# ARC_Shield_0_1.net
KiCad netlist of a schematic drawn in EAGLE
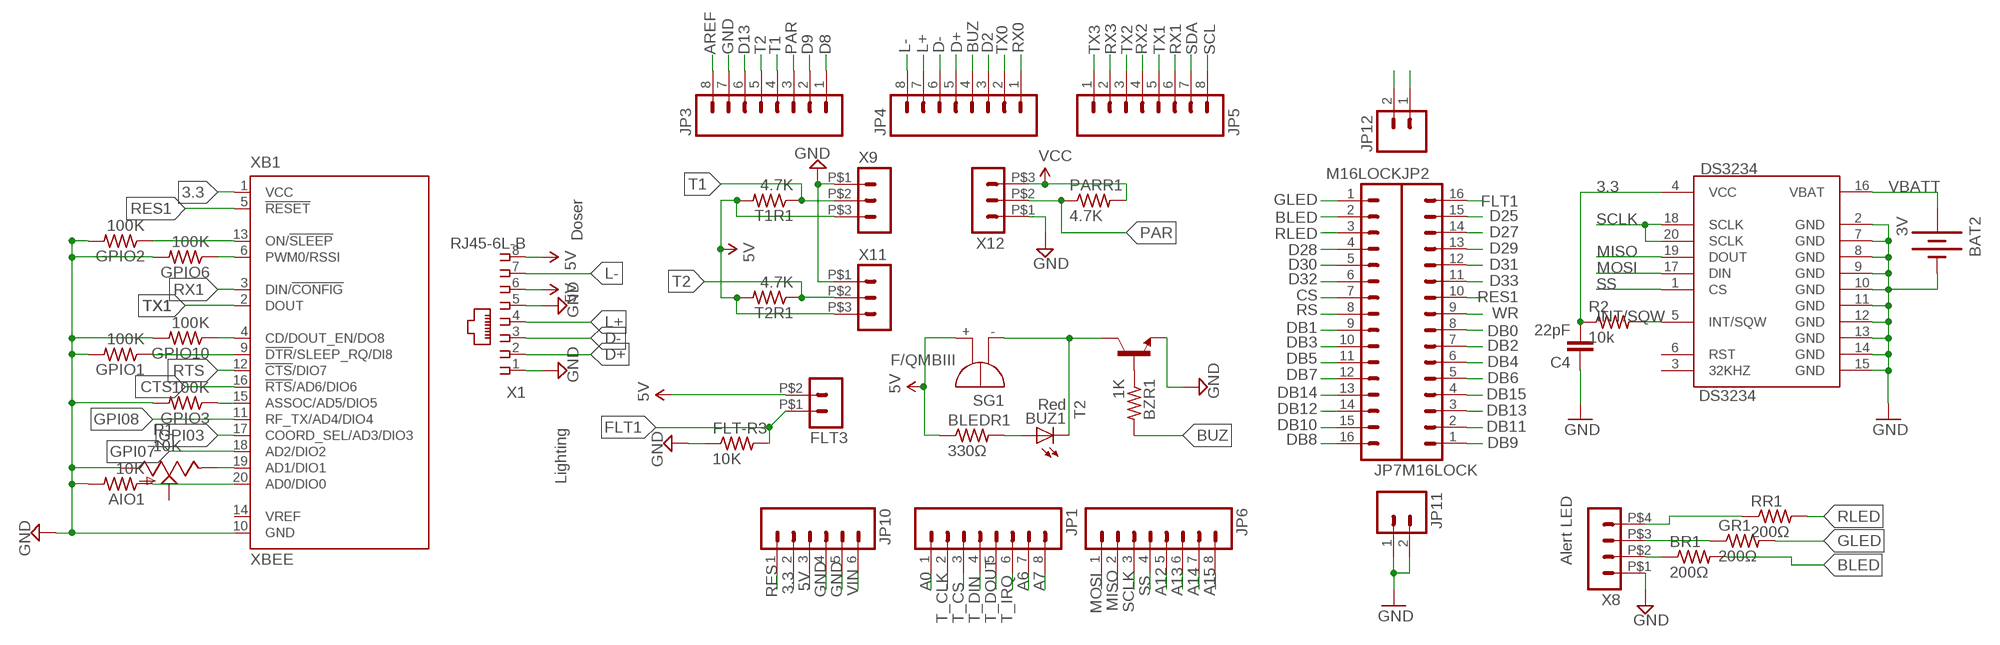
[diagram p0: schematic, sheet 1]

(export (version "E")
  (design (tool "Eeschema 10.0.6"))
  (components
    (comp (ref "AIO1")
      (value "10K")
      (footprint "eagle-import:0204_7")
      (libsource (lib "eagle-import") (part "R-US_0204/7"))
    )
    (comp (ref "BAT2")
      (value "3V")
      (footprint "eagle-import:BATTCON_12MM_CURVED")
      (libsource (lib "eagle-import") (part "BATTERY"))
    )
    (comp (ref "BLEDR1")
      (value "330Ω")
      (footprint "eagle-import:0204_7")
      (libsource (lib "eagle-import") (part "R-US_0204/7"))
    )
    (comp (ref "BR1")
      (value "200Ω")
      (footprint "eagle-import:0204_7")
      (libsource (lib "eagle-import") (part "R-US_0204/7"))
    )
    (comp (ref "BUZ1")
      (value "Red")
      (footprint "eagle-import:LED3MM")
      (libsource (lib "eagle-import") (part "LED3MM"))
    )
    (comp (ref "BZR1")
      (value "1K")
      (footprint "eagle-import:0204_7")
      (libsource (lib "eagle-import") (part "R-US_0204/7"))
    )
    (comp (ref "C4")
      (value "22pF")
      (footprint "eagle-import:C5B3")
      (libsource (lib "eagle-import") (part "C5/3"))
    )
    (comp (ref "DS3234")
      (value "DS3234")
      (footprint "eagle-import:DS3234")
      (libsource (lib "eagle-import") (part "DS3234"))
    )
    (comp (ref "FLT-R3")
      (value "10K")
      (footprint "eagle-import:0204_7")
      (libsource (lib "eagle-import") (part "R-US_0204/7"))
    )
    (comp (ref "FLT3")
      (value "HEADER_POS2_43045-0200")
      (footprint "eagle-import:43045-0200")
      (libsource (lib "eagle-import") (part "HEADER_POS2_?43045-0200"))
    )
    (comp (ref "GPIO1")
      (value "100K")
      (footprint "eagle-import:0204_7")
      (libsource (lib "eagle-import") (part "R-US_0204/7"))
    )
    (comp (ref "GPIO2")
      (value "100K")
      (footprint "eagle-import:0204_7")
      (libsource (lib "eagle-import") (part "R-US_0204/7"))
    )
    (comp (ref "GPIO3")
      (value "100K")
      (footprint "eagle-import:0204_7")
      (libsource (lib "eagle-import") (part "R-US_0204/7"))
    )
    (comp (ref "GPIO6")
      (value "100K")
      (footprint "eagle-import:0204_7")
      (libsource (lib "eagle-import") (part "R-US_0204/7"))
    )
    (comp (ref "GPIO10")
      (value "100K")
      (footprint "eagle-import:0204_7")
      (libsource (lib "eagle-import") (part "R-US_0204/7"))
    )
    (comp (ref "GR1")
      (value "200Ω")
      (footprint "eagle-import:0204_7")
      (libsource (lib "eagle-import") (part "R-US_0204/7"))
    )
    (comp (ref "JP1")
      (value "M08LOCK")
      (footprint "eagle-import:1X08_LOCK")
      (libsource (lib "eagle-import") (part "M08LOCK"))
    )
    (comp (ref "JP2")
      (value "M16LOCK")
      (footprint "eagle-import:1X16_LOCK")
      (libsource (lib "eagle-import") (part "M16LOCK"))
    )
    (comp (ref "JP3")
      (value "M08LOCK")
      (footprint "eagle-import:1X08_LOCK")
      (libsource (lib "eagle-import") (part "M08LOCK"))
    )
    (comp (ref "JP4")
      (value "M08LOCK")
      (footprint "eagle-import:1X08_LOCK")
      (libsource (lib "eagle-import") (part "M08LOCK"))
    )
    (comp (ref "JP5")
      (value "M08LOCK")
      (footprint "eagle-import:1X08_LOCK")
      (libsource (lib "eagle-import") (part "M08LOCK"))
    )
    (comp (ref "JP6")
      (value "M08LOCK")
      (footprint "eagle-import:1X08_LOCK")
      (libsource (lib "eagle-import") (part "M08LOCK"))
    )
    (comp (ref "JP7")
      (value "M16LOCK")
      (footprint "eagle-import:1X16_LOCK")
      (libsource (lib "eagle-import") (part "M16LOCK"))
    )
    (comp (ref "JP10")
      (value "M06LOCK")
      (footprint "eagle-import:1X06_LOCK")
      (libsource (lib "eagle-import") (part "M06LOCK"))
    )
    (comp (ref "JP11")
      (value "M02LOCK")
      (footprint "eagle-import:1X02_LOCK")
      (libsource (lib "eagle-import") (part "M02LOCK"))
    )
    (comp (ref "JP12")
      (value "M02LOCK")
      (footprint "eagle-import:1X02_LOCK")
      (libsource (lib "eagle-import") (part "M02LOCK"))
    )
    (comp (ref "PARR1")
      (value "4.7K")
      (footprint "eagle-import:0204_7")
      (libsource (lib "eagle-import") (part "R-US_0204/7"))
    )
    (comp (ref "R1")
      (value "10K")
      (footprint "eagle-import:B25U")
      (libsource (lib "eagle-import") (part "TRIM_US-B25U"))
    )
    (comp (ref "R2")
      (value "10k")
      (footprint "eagle-import:0204_7")
      (libsource (lib "eagle-import") (part "R-US_0204/7"))
    )
    (comp (ref "RR1")
      (value "200Ω")
      (footprint "eagle-import:0204_7")
      (libsource (lib "eagle-import") (part "R-US_0204/7"))
    )
    (comp (ref "SG1")
      (value "F/QMBIII")
      (footprint "eagle-import:F_QMBIII")
      (libsource (lib "eagle-import") (part "F/QMBIII"))
    )
    (comp (ref "T1R1")
      (value "4.7K")
      (footprint "eagle-import:0204_7")
      (libsource (lib "eagle-import") (part "R-US_0204/7"))
    )
    (comp (ref "T2")
      (value "-NPN-TO92")
      (footprint "eagle-import:TO92")
      (libsource (lib "eagle-import") (part "-NPN-TO92"))
    )
    (comp (ref "T2R1")
      (value "4.7K")
      (footprint "eagle-import:0204_7")
      (libsource (lib "eagle-import") (part "R-US_0204/7"))
    )
    (comp (ref "X1")
      (value "RJ45-6L-B")
      (footprint "eagle-import:RJ45-NO-SHIELD")
      (libsource (lib "eagle-import") (part "RJ45-6L-B"))
    )
    (comp (ref "X8")
      (value "HEADER_POS4_43045-0401")
      (footprint "eagle-import:43045-0400")
      (libsource (lib "eagle-import") (part "HEADER_POS4_?43045-0401"))
    )
    (comp (ref "X9")
      (value "HEADER_POS3_43650-0300")
      (footprint "eagle-import:43650-0300")
      (libsource (lib "eagle-import") (part "HEADER_POS3_?43650-0300"))
    )
    (comp (ref "X11")
      (value "HEADER_POS3_43650-0300")
      (footprint "eagle-import:43650-0300")
      (libsource (lib "eagle-import") (part "HEADER_POS3_?43650-0300"))
    )
    (comp (ref "X12")
      (value "HEADER_POS3_43650-0300")
      (footprint "eagle-import:43650-0300")
      (libsource (lib "eagle-import") (part "HEADER_POS3_?43650-0300"))
    )
    (comp (ref "XB1")
      (value "XBEE")
      (footprint "eagle-import:XBEE")
      (fields (field (name "MPN") "XBP24-Z7UIT-004"))
      (libsource (lib "eagle-import") (part "XBEE"))
    )
  )
  (nets
    (net (code "1") (name "/5V@1") (class "Default")
      (node (ref "JP12") (pin "1") (pinfunction "1_1") (pintype "passive"))
      (node (ref "JP12") (pin "2") (pinfunction "2_2") (pintype "passive"))
    )
    (net (code "2") (name "/A0") (class "Default")
      (node (ref "JP1") (pin "1") (pinfunction "1_1") (pintype "passive"))
    )
    (net (code "3") (name "/A6") (class "Default")
      (node (ref "JP1") (pin "7") (pinfunction "7_7") (pintype "passive"))
    )
    (net (code "4") (name "/A7") (class "Default")
      (node (ref "JP1") (pin "8") (pinfunction "8_8") (pintype "passive"))
    )
    (net (code "5") (name "/A12") (class "Default")
      (node (ref "JP6") (pin "5") (pinfunction "5_5") (pintype "passive"))
    )
    (net (code "6") (name "/A13") (class "Default")
      (node (ref "JP6") (pin "6") (pinfunction "6_6") (pintype "passive"))
    )
    (net (code "7") (name "/A14") (class "Default")
      (node (ref "JP6") (pin "7") (pinfunction "7_7") (pintype "passive"))
    )
    (net (code "8") (name "/A15") (class "Default")
      (node (ref "JP6") (pin "8") (pinfunction "8_8") (pintype "passive"))
    )
    (net (code "9") (name "/AREF") (class "Default")
      (node (ref "JP3") (pin "8") (pinfunction "8_8") (pintype "passive"))
    )
    (net (code "10") (name "/CS") (class "Default")
      (node (ref "JP7") (pin "7") (pinfunction "7_7") (pintype "passive"))
    )
    (net (code "11") (name "/D2") (class "Default")
      (node (ref "JP4") (pin "3") (pinfunction "3_3") (pintype "passive"))
    )
    (net (code "12") (name "/D8") (class "Default")
      (node (ref "JP3") (pin "1") (pinfunction "1_1") (pintype "passive"))
    )
    (net (code "13") (name "/D9") (class "Default")
      (node (ref "JP3") (pin "2") (pinfunction "2_2") (pintype "passive"))
    )
    (net (code "14") (name "/D13") (class "Default")
      (node (ref "JP3") (pin "6") (pinfunction "6_6") (pintype "passive"))
    )
    (net (code "15") (name "/D25") (class "Default")
      (node (ref "JP2") (pin "15") (pinfunction "15_15") (pintype "passive"))
    )
    (net (code "16") (name "/D27") (class "Default")
      (node (ref "JP2") (pin "14") (pinfunction "14_14") (pintype "passive"))
    )
    (net (code "17") (name "/D28") (class "Default")
      (node (ref "JP7") (pin "4") (pinfunction "4_4") (pintype "passive"))
    )
    (net (code "18") (name "/D29") (class "Default")
      (node (ref "JP2") (pin "13") (pinfunction "13_13") (pintype "passive"))
    )
    (net (code "19") (name "/D30") (class "Default")
      (node (ref "JP7") (pin "5") (pinfunction "5_5") (pintype "passive"))
    )
    (net (code "20") (name "/D31") (class "Default")
      (node (ref "JP2") (pin "12") (pinfunction "12_12") (pintype "passive"))
    )
    (net (code "21") (name "/D32") (class "Default")
      (node (ref "JP7") (pin "6") (pinfunction "6_6") (pintype "passive"))
    )
    (net (code "22") (name "/D33") (class "Default")
      (node (ref "JP2") (pin "11") (pinfunction "11_11") (pintype "passive"))
    )
    (net (code "23") (name "/DB0") (class "Default")
      (node (ref "JP2") (pin "8") (pinfunction "8_8") (pintype "passive"))
    )
    (net (code "24") (name "/DB1") (class "Default")
      (node (ref "JP7") (pin "9") (pinfunction "9_9") (pintype "passive"))
    )
    (net (code "25") (name "/DB2") (class "Default")
      (node (ref "JP2") (pin "7") (pinfunction "7_7") (pintype "passive"))
    )
    (net (code "26") (name "/DB3") (class "Default")
      (node (ref "JP7") (pin "10") (pinfunction "10_10") (pintype "passive"))
    )
    (net (code "27") (name "/DB4") (class "Default")
      (node (ref "JP2") (pin "6") (pinfunction "6_6") (pintype "passive"))
    )
    (net (code "28") (name "/DB5") (class "Default")
      (node (ref "JP7") (pin "11") (pinfunction "11_11") (pintype "passive"))
    )
    (net (code "29") (name "/DB6") (class "Default")
      (node (ref "JP2") (pin "5") (pinfunction "5_5") (pintype "passive"))
    )
    (net (code "30") (name "/DB7") (class "Default")
      (node (ref "JP7") (pin "12") (pinfunction "12_12") (pintype "passive"))
    )
    (net (code "31") (name "/DB8") (class "Default")
      (node (ref "JP7") (pin "16") (pinfunction "16_16") (pintype "passive"))
    )
    (net (code "32") (name "/DB9") (class "Default")
      (node (ref "JP2") (pin "1") (pinfunction "1_1") (pintype "passive"))
    )
    (net (code "33") (name "/DB10") (class "Default")
      (node (ref "JP7") (pin "15") (pinfunction "15_15") (pintype "passive"))
    )
    (net (code "34") (name "/DB11") (class "Default")
      (node (ref "JP2") (pin "2") (pinfunction "2_2") (pintype "passive"))
    )
    (net (code "35") (name "/DB12") (class "Default")
      (node (ref "JP7") (pin "14") (pinfunction "14_14") (pintype "passive"))
    )
    (net (code "36") (name "/DB13") (class "Default")
      (node (ref "JP2") (pin "3") (pinfunction "3_3") (pintype "passive"))
    )
    (net (code "37") (name "/DB14") (class "Default")
      (node (ref "JP7") (pin "13") (pinfunction "13_13") (pintype "passive"))
    )
    (net (code "38") (name "/DB15") (class "Default")
      (node (ref "JP2") (pin "4") (pinfunction "4_4") (pintype "passive"))
    )
    (net (code "39") (name "/INT{slash}SQW") (class "Default")
      (node (ref "DS3234") (pin "5") (pinfunction "INT/SQW_5") (pintype "bidirectional"))
      (node (ref "R2") (pin "2") (pinfunction "2_2") (pintype "passive"))
    )
    (net (code "40") (name "/MISO") (class "Default")
      (node (ref "DS3234") (pin "19") (pinfunction "DOUT_19") (pintype "bidirectional"))
      (node (ref "JP6") (pin "2") (pinfunction "2_2") (pintype "passive"))
    )
    (net (code "41") (name "/MOSI") (class "Default")
      (node (ref "DS3234") (pin "17") (pinfunction "DIN_17") (pintype "bidirectional"))
      (node (ref "JP6") (pin "1") (pinfunction "1_1") (pintype "passive"))
    )
    (net (code "42") (name "/RES") (class "Default")
      (node (ref "JP10") (pin "1") (pinfunction "1_1") (pintype "passive"))
    )
    (net (code "43") (name "/RS") (class "Default")
      (node (ref "JP7") (pin "8") (pinfunction "8_8") (pintype "passive"))
    )
    (net (code "44") (name "/RX0") (class "Default")
      (node (ref "JP4") (pin "1") (pinfunction "1_1") (pintype "passive"))
    )
    (net (code "45") (name "/RX2") (class "Default")
      (node (ref "JP5") (pin "4") (pinfunction "4_4") (pintype "passive"))
    )
    (net (code "46") (name "/RX3") (class "Default")
      (node (ref "JP5") (pin "2") (pinfunction "2_2") (pintype "passive"))
    )
    (net (code "47") (name "/SCL") (class "Default")
      (node (ref "JP5") (pin "8") (pinfunction "8_8") (pintype "passive"))
    )
    (net (code "48") (name "/SCLK") (class "Default")
      (node (ref "DS3234") (pin "18") (pinfunction "SCLK_18") (pintype "bidirectional"))
      (node (ref "DS3234") (pin "20") (pinfunction "SCLK_20") (pintype "bidirectional"))
      (node (ref "JP6") (pin "3") (pinfunction "3_3") (pintype "passive"))
    )
    (net (code "49") (name "/SDA") (class "Default")
      (node (ref "JP5") (pin "7") (pinfunction "7_7") (pintype "passive"))
    )
    (net (code "50") (name "/SS") (class "Default")
      (node (ref "DS3234") (pin "1") (pinfunction "CS_1") (pintype "bidirectional"))
      (node (ref "JP6") (pin "4") (pinfunction "4_4") (pintype "passive"))
    )
    (net (code "51") (name "/TX0") (class "Default")
      (node (ref "JP4") (pin "2") (pinfunction "2_2") (pintype "passive"))
    )
    (net (code "52") (name "/TX2") (class "Default")
      (node (ref "JP5") (pin "3") (pinfunction "3_3") (pintype "passive"))
    )
    (net (code "53") (name "/TX3") (class "Default")
      (node (ref "JP5") (pin "1") (pinfunction "1_1") (pintype "passive"))
    )
    (net (code "54") (name "/T_CLK") (class "Default")
      (node (ref "JP1") (pin "2") (pinfunction "2_2") (pintype "passive"))
    )
    (net (code "55") (name "/T_CS") (class "Default")
      (node (ref "JP1") (pin "3") (pinfunction "3_3") (pintype "passive"))
    )
    (net (code "56") (name "/T_DIN") (class "Default")
      (node (ref "JP1") (pin "4") (pinfunction "4_4") (pintype "passive"))
    )
    (net (code "57") (name "/T_DOUT") (class "Default")
      (node (ref "JP1") (pin "5") (pinfunction "5_5") (pintype "passive"))
    )
    (net (code "58") (name "/T_IRQ") (class "Default")
      (node (ref "JP1") (pin "6") (pinfunction "6_6") (pintype "passive"))
    )
    (net (code "59") (name "/VBATT") (class "Default")
      (node (ref "BAT2") (pin "PWR@1") (pinfunction "+_PWR@1") (pintype "power_in"))
      (node (ref "DS3234") (pin "16") (pinfunction "VBAT_16") (pintype "bidirectional"))
    )
    (net (code "60") (name "/VIN") (class "Default")
      (node (ref "JP10") (pin "6") (pinfunction "6_6") (pintype "passive"))
    )
    (net (code "61") (name "/WR") (class "Default")
      (node (ref "JP2") (pin "9") (pinfunction "9_9") (pintype "passive"))
    )
    (net (code "62") (name "3.3") (class "Default")
      (node (ref "C4") (pin "2") (pinfunction "2_2") (pintype "passive"))
      (node (ref "DS3234") (pin "4") (pinfunction "VCC_4") (pintype "bidirectional"))
      (node (ref "JP10") (pin "2") (pinfunction "2_2") (pintype "passive"))
      (node (ref "R2") (pin "1") (pinfunction "1_1") (pintype "passive"))
      (node (ref "XB1") (pin "1") (pinfunction "VCC_1") (pintype "power_in"))
    )
    (net (code "63") (name "5V") (class "Default")
      (node (ref "BLEDR1") (pin "1") (pinfunction "1_1") (pintype "passive"))
      (node (ref "FLT3") (pin "P$2") (pinfunction "2_P$2") (pintype "passive"))
      (node (ref "JP10") (pin "3") (pinfunction "3_3") (pintype "passive"))
      (node (ref "PARR1") (pin "2") (pinfunction "2_2") (pintype "passive"))
      (node (ref "SG1") (pin "+") (pinfunction "-_+") (pintype "passive"))
      (node (ref "T1R1") (pin "2") (pinfunction "2_2") (pintype "passive"))
      (node (ref "T2R1") (pin "2") (pinfunction "2_2") (pintype "passive"))
      (node (ref "X1") (pin "6") (pinfunction "6_6") (pintype "passive"))
      (node (ref "X1") (pin "8") (pinfunction "8_8") (pintype "passive"))
      (node (ref "X11") (pin "P$3") (pinfunction "3_P$3") (pintype "passive"))
      (node (ref "X12") (pin "P$3") (pinfunction "3_P$3") (pintype "passive"))
      (node (ref "X9") (pin "P$3") (pinfunction "3_P$3") (pintype "passive"))
    )
    (net (code "64") (name "BLED") (class "Default")
      (node (ref "BR1") (pin "2") (pinfunction "2_2") (pintype "passive"))
      (node (ref "JP7") (pin "2") (pinfunction "2_2") (pintype "passive"))
    )
    (net (code "65") (name "BUZ") (class "Default")
      (node (ref "BZR1") (pin "2") (pinfunction "2_2") (pintype "passive"))
      (node (ref "JP4") (pin "4") (pinfunction "4_4") (pintype "passive"))
    )
    (net (code "66") (name "CTS") (class "Default")
      (node (ref "XB1") (pin "16") (pinfunction "~{RTS}/AD6/DIO6_16") (pintype "bidirectional"))
    )
    (net (code "67") (name "D+") (class "Default")
      (node (ref "JP4") (pin "5") (pinfunction "5_5") (pintype "passive"))
      (node (ref "X1") (pin "2") (pinfunction "2_2") (pintype "passive"))
    )
    (net (code "68") (name "D-") (class "Default")
      (node (ref "JP4") (pin "6") (pinfunction "6_6") (pintype "passive"))
      (node (ref "X1") (pin "3") (pinfunction "3_3") (pintype "passive"))
    )
    (net (code "69") (name "FLT1") (class "Default")
      (node (ref "FLT-R3") (pin "2") (pinfunction "2_2") (pintype "passive"))
      (node (ref "FLT3") (pin "P$1") (pinfunction "1_P$1") (pintype "passive"))
      (node (ref "JP2") (pin "16") (pinfunction "16_16") (pintype "passive"))
    )
    (net (code "70") (name "GLED") (class "Default")
      (node (ref "GR1") (pin "2") (pinfunction "2_2") (pintype "passive"))
      (node (ref "JP7") (pin "1") (pinfunction "1_1") (pintype "passive"))
    )
    (net (code "71") (name "GND") (class "Default")
      (node (ref "AIO1") (pin "2") (pinfunction "2_2") (pintype "passive"))
      (node (ref "BAT2") (pin "GND") (pinfunction "-_GND") (pintype "power_in"))
      (node (ref "C4") (pin "1") (pinfunction "1_1") (pintype "passive"))
      (node (ref "DS3234") (pin "10") (pinfunction "GND_10") (pintype "bidirectional"))
      (node (ref "DS3234") (pin "11") (pinfunction "GND_11") (pintype "bidirectional"))
      (node (ref "DS3234") (pin "12") (pinfunction "GND_12") (pintype "bidirectional"))
      (node (ref "DS3234") (pin "13") (pinfunction "GND_13") (pintype "bidirectional"))
      (node (ref "DS3234") (pin "14") (pinfunction "GND_14") (pintype "bidirectional"))
      (node (ref "DS3234") (pin "15") (pinfunction "GND_15") (pintype "bidirectional"))
      (node (ref "DS3234") (pin "2") (pinfunction "GND_2") (pintype "bidirectional"))
      (node (ref "DS3234") (pin "7") (pinfunction "GND_7") (pintype "bidirectional"))
      (node (ref "DS3234") (pin "8") (pinfunction "GND_8") (pintype "bidirectional"))
      (node (ref "DS3234") (pin "9") (pinfunction "GND_9") (pintype "bidirectional"))
      (node (ref "FLT-R3") (pin "1") (pinfunction "1_1") (pintype "passive"))
      (node (ref "GPIO1") (pin "2") (pinfunction "2_2") (pintype "passive"))
      (node (ref "GPIO10") (pin "2") (pinfunction "2_2") (pintype "passive"))
      (node (ref "GPIO2") (pin "2") (pinfunction "2_2") (pintype "passive"))
      (node (ref "GPIO3") (pin "2") (pinfunction "2_2") (pintype "passive"))
      (node (ref "GPIO6") (pin "2") (pinfunction "2_2") (pintype "passive"))
      (node (ref "JP10") (pin "4") (pinfunction "4_4") (pintype "passive"))
      (node (ref "JP10") (pin "5") (pinfunction "5_5") (pintype "passive"))
      (node (ref "JP11") (pin "1") (pinfunction "1_1") (pintype "passive"))
      (node (ref "JP11") (pin "2") (pinfunction "2_2") (pintype "passive"))
      (node (ref "JP3") (pin "7") (pinfunction "7_7") (pintype "passive"))
      (node (ref "R1") (pin "A") (pinfunction "A_A") (pintype "passive"))
      (node (ref "T2") (pin "1") (pinfunction "E_1") (pintype "passive"))
      (node (ref "X1") (pin "1") (pinfunction "1_1") (pintype "passive"))
      (node (ref "X1") (pin "5") (pinfunction "5_5") (pintype "passive"))
      (node (ref "X11") (pin "P$1") (pinfunction "1_P$1") (pintype "passive"))
      (node (ref "X12") (pin "P$1") (pinfunction "1_P$1") (pintype "passive"))
      (node (ref "X8") (pin "P$1") (pinfunction "1_P$1") (pintype "passive"))
      (node (ref "X9") (pin "P$1") (pinfunction "1_P$1") (pintype "passive"))
      (node (ref "XB1") (pin "10") (pinfunction "GND_10") (pintype "power_in"))
    )
    (net (code "72") (name "GPI03") (class "Default")
      (node (ref "XB1") (pin "17") (pinfunction "COORD_SEL/AD3/DIO3_17") (pintype "bidirectional"))
    )
    (net (code "73") (name "GPI07") (class "Default")
      (node (ref "XB1") (pin "18") (pinfunction "AD2/DIO2_18") (pintype "bidirectional"))
    )
    (net (code "74") (name "GPI08") (class "Default")
      (node (ref "XB1") (pin "11") (pinfunction "RF_TX/AD4/DIO4_11") (pintype "bidirectional"))
    )
    (net (code "75") (name "L+") (class "Default")
      (node (ref "JP4") (pin "7") (pinfunction "7_7") (pintype "passive"))
      (node (ref "X1") (pin "4") (pinfunction "4_4") (pintype "passive"))
    )
    (net (code "76") (name "L-") (class "Default")
      (node (ref "JP4") (pin "8") (pinfunction "8_8") (pintype "passive"))
      (node (ref "X1") (pin "7") (pinfunction "7_7") (pintype "passive"))
    )
    (net (code "77") (name "Net-(BLEDR1-Pad2)") (class "Default")
      (node (ref "BLEDR1") (pin "2") (pinfunction "2_2") (pintype "passive"))
      (node (ref "BUZ1") (pin "A") (pinfunction "A_A") (pintype "passive"))
    )
    (net (code "78") (name "Net-(BUZ1-C)") (class "Default")
      (node (ref "BUZ1") (pin "K") (pinfunction "C_K") (pintype "passive"))
      (node (ref "SG1") (pin "-") (pinfunction "+_-") (pintype "passive"))
      (node (ref "T2") (pin "3") (pinfunction "C_3") (pintype "passive"))
    )
    (net (code "79") (name "Net-(T2-B)") (class "Default")
      (node (ref "BZR1") (pin "1") (pinfunction "1_1") (pintype "passive"))
      (node (ref "T2") (pin "2") (pinfunction "B_2") (pintype "passive"))
    )
    (net (code "80") (name "Net-(X8-2)") (class "Default")
      (node (ref "BR1") (pin "1") (pinfunction "1_1") (pintype "passive"))
      (node (ref "X8") (pin "P$2") (pinfunction "2_P$2") (pintype "passive"))
    )
    (net (code "81") (name "Net-(X8-3)") (class "Default")
      (node (ref "GR1") (pin "1") (pinfunction "1_1") (pintype "passive"))
      (node (ref "X8") (pin "P$3") (pinfunction "3_P$3") (pintype "passive"))
    )
    (net (code "82") (name "Net-(X8-4)") (class "Default")
      (node (ref "RR1") (pin "1") (pinfunction "1_1") (pintype "passive"))
      (node (ref "X8") (pin "P$4") (pinfunction "4_P$4") (pintype "passive"))
    )
    (net (code "83") (name "Net-(XB1-AD0{slash}DIO0)") (class "Default")
      (node (ref "AIO1") (pin "1") (pinfunction "1_1") (pintype "passive"))
      (node (ref "XB1") (pin "20") (pinfunction "AD0/DIO0_20") (pintype "bidirectional"))
    )
    (net (code "84") (name "Net-(XB1-AD1{slash}DIO1)") (class "Default")
      (node (ref "R1") (pin "E") (pinfunction "E_E") (pintype "passive"))
      (node (ref "XB1") (pin "19") (pinfunction "AD1/DIO1_19") (pintype "bidirectional"))
    )
    (net (code "85") (name "Net-(XB1-ASSOC{slash}AD5{slash}DIO5)") (class "Default")
      (node (ref "GPIO3") (pin "1") (pinfunction "1_1") (pintype "passive"))
      (node (ref "XB1") (pin "15") (pinfunction "ASSOC/AD5/DIO5_15") (pintype "bidirectional"))
    )
    (net (code "86") (name "Net-(XB1-CD{slash}DOUT_EN{slash}DO8)") (class "Default")
      (node (ref "GPIO10") (pin "1") (pinfunction "1_1") (pintype "passive"))
      (node (ref "XB1") (pin "4") (pinfunction "CD/DOUT_EN/DO8_4") (pintype "output"))
    )
    (net (code "87") (name "Net-(XB1-ON{slash}~{SLEEP})") (class "Default")
      (node (ref "GPIO2") (pin "1") (pinfunction "1_1") (pintype "passive"))
      (node (ref "XB1") (pin "13") (pinfunction "ON/~{SLEEP}_13") (pintype "output"))
    )
    (net (code "88") (name "Net-(XB1-PWM0{slash}RSSI)") (class "Default")
      (node (ref "GPIO6") (pin "1") (pinfunction "1_1") (pintype "passive"))
      (node (ref "XB1") (pin "6") (pinfunction "PWM0/RSSI_6") (pintype "output"))
    )
    (net (code "89") (name "Net-(XB1-~{DTR}{slash}SLEEP_RQ{slash}DI8)") (class "Default")
      (node (ref "GPIO1") (pin "1") (pinfunction "1_1") (pintype "passive"))
      (node (ref "XB1") (pin "9") (pinfunction "~{DTR}/SLEEP_RQ/DI8_9") (pintype "bidirectional"))
    )
    (net (code "90") (name "PAR") (class "Default")
      (node (ref "JP3") (pin "3") (pinfunction "3_3") (pintype "passive"))
      (node (ref "PARR1") (pin "1") (pinfunction "1_1") (pintype "passive"))
      (node (ref "X12") (pin "P$2") (pinfunction "2_P$2") (pintype "passive"))
    )
    (net (code "91") (name "RES1") (class "Default")
      (node (ref "JP2") (pin "10") (pinfunction "10_10") (pintype "passive"))
      (node (ref "XB1") (pin "5") (pinfunction "~{RESET}_5") (pintype "input"))
    )
    (net (code "92") (name "RLED") (class "Default")
      (node (ref "JP7") (pin "3") (pinfunction "3_3") (pintype "passive"))
      (node (ref "RR1") (pin "2") (pinfunction "2_2") (pintype "passive"))
    )
    (net (code "93") (name "RTS") (class "Default")
      (node (ref "XB1") (pin "12") (pinfunction "~{CTS}/DIO7_12") (pintype "bidirectional"))
    )
    (net (code "94") (name "RX1") (class "Default")
      (node (ref "JP5") (pin "6") (pinfunction "6_6") (pintype "passive"))
      (node (ref "XB1") (pin "3") (pinfunction "DIN/~{CONFIG}_3") (pintype "input"))
    )
    (net (code "95") (name "T1") (class "Default")
      (node (ref "JP3") (pin "4") (pinfunction "4_4") (pintype "passive"))
      (node (ref "T1R1") (pin "1") (pinfunction "1_1") (pintype "passive"))
      (node (ref "X9") (pin "P$2") (pinfunction "2_P$2") (pintype "passive"))
    )
    (net (code "96") (name "T2") (class "Default")
      (node (ref "JP3") (pin "5") (pinfunction "5_5") (pintype "passive"))
      (node (ref "T2R1") (pin "1") (pinfunction "1_1") (pintype "passive"))
      (node (ref "X11") (pin "P$2") (pinfunction "2_P$2") (pintype "passive"))
    )
    (net (code "97") (name "TX1") (class "Default")
      (node (ref "JP5") (pin "5") (pinfunction "5_5") (pintype "passive"))
      (node (ref "XB1") (pin "2") (pinfunction "DOUT_2") (pintype "output"))
    )
    (net (code "98") (name "unconnected-(DS3234-32KHZ-Pad3)") (class "Default")
      (node (ref "DS3234") (pin "3") (pinfunction "32KHZ_3") (pintype "bidirectional"))
    )
    (net (code "99") (name "unconnected-(DS3234-RST-Pad6)") (class "Default")
      (node (ref "DS3234") (pin "6") (pinfunction "RST_6") (pintype "bidirectional"))
    )
    (net (code "100") (name "unconnected-(R1-PadS)") (class "Default")
      (node (ref "R1") (pin "S") (pinfunction "S_S") (pintype "passive"))
    )
    (net (code "101") (name "unconnected-(XB1-VREF-Pad14)") (class "Default")
      (node (ref "XB1") (pin "14") (pinfunction "VREF_14") (pintype "input"))
    )
  )
)
